# rec_seeed.net
KiCad netlist of a schematic drawn in EAGLE
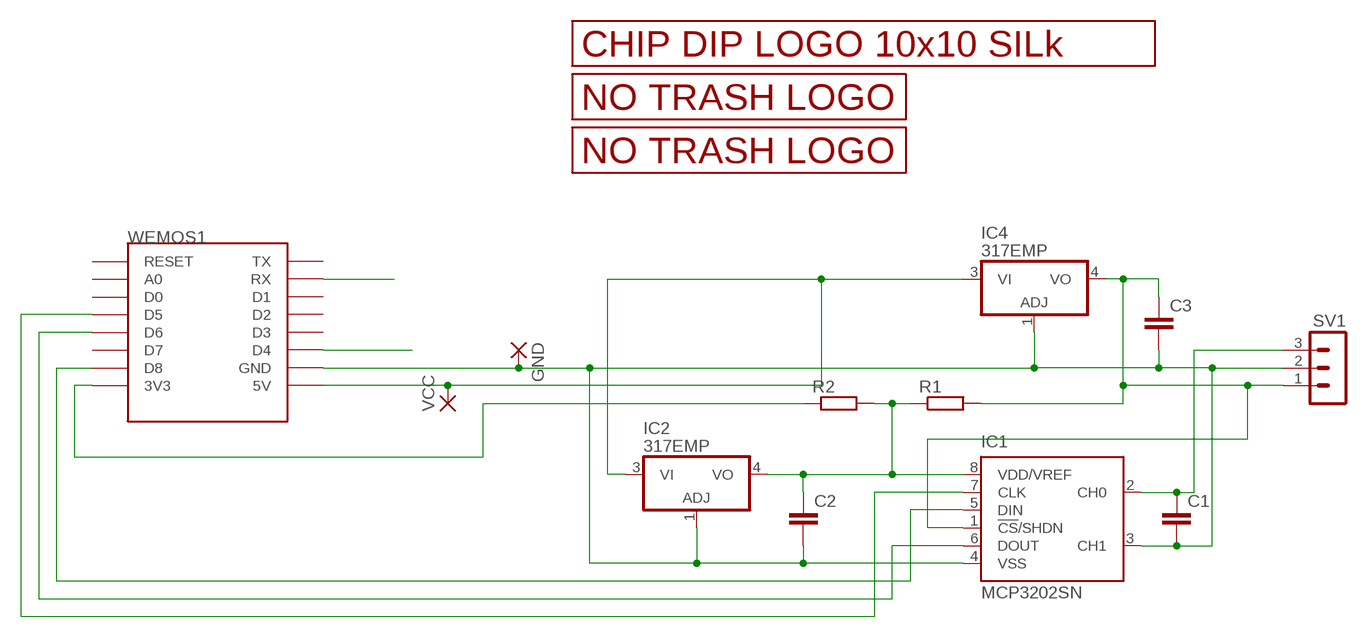
[diagram p0: schematic, sheet 1]

(export (version "E")
  (design (tool "Eeschema 10.0.6"))
  (components
    (comp (ref "C1")
      (value "C-EUC0805")
      (footprint "eagle-import:C0805")
      (libsource (lib "eagle-import") (part "C-EUC0805"))
    )
    (comp (ref "C2")
      (value "C-EUC0805")
      (footprint "eagle-import:C0805")
      (libsource (lib "eagle-import") (part "C-EUC0805"))
    )
    (comp (ref "C3")
      (value "C-EUC0805")
      (footprint "eagle-import:C0805")
      (libsource (lib "eagle-import") (part "C-EUC0805"))
    )
    (comp (ref "GND")
      (value "SMD1.36X3")
      (footprint "eagle-import:SMD1,36-3")
      (libsource (lib "eagle-import") (part "SMD1.36X3"))
    )
    (comp (ref "IC1")
      (value "MCP3202SN")
      (footprint "eagle-import:SO-08")
      (fields (field (name "MF") "MICROCHIP") (field (name "MPN") "MCP3202-CI/SN"))
      (libsource (lib "eagle-import") (part "MCP3202SN"))
    )
    (comp (ref "IC2")
      (value "317EMP")
      (footprint "eagle-import:SOT223")
      (libsource (lib "eagle-import") (part "317EMP"))
    )
    (comp (ref "IC4")
      (value "317EMP")
      (footprint "eagle-import:SOT223")
      (libsource (lib "eagle-import") (part "317EMP"))
    )
    (comp (ref "R1")
      (value "R-EU_M0805")
      (footprint "eagle-import:M0805")
      (libsource (lib "eagle-import") (part "R-EU_M0805"))
    )
    (comp (ref "R2")
      (value "R-EU_M0805")
      (footprint "eagle-import:M0805")
      (libsource (lib "eagle-import") (part "R-EU_M0805"))
    )
    (comp (ref "SV1")
      (value "MA03-1")
      (footprint "eagle-import:MA03-1")
      (libsource (lib "eagle-import") (part "MA03-1"))
    )
    (comp (ref "U$1")
      (value "LOGO_NO_TRASHNO_TRASH")
      (footprint "eagle-import:LOGO_ROHS_NO_TRASH")
      (libsource (lib "eagle-import") (part "LOGO_NO_TRASHNO_TRASH"))
    )
    (comp (ref "U$2")
      (value "LOGO_10X10_SILK")
      (footprint "eagle-import:LOGO2_10X10_SILK")
      (libsource (lib "eagle-import") (part "LOGO_10X10_SILK"))
    )
    (comp (ref "U$3")
      (value "LOGO_NO_TRASHROHS")
      (footprint "eagle-import:LOGO_ROHS_SYM")
      (libsource (lib "eagle-import") (part "LOGO_NO_TRASHROHS"))
    )
    (comp (ref "VCC")
      (value "SMD1.36X3")
      (footprint "eagle-import:SMD1,36-3")
      (libsource (lib "eagle-import") (part "SMD1.36X3"))
    )
    (comp (ref "WEMOS1")
      (value "WEMOS-D1-MININOTXT")
      (footprint "eagle-import:WEMOS_D1_MINI_NOTXT")
      (libsource (lib "eagle-import") (part "WEMOS-D1-MININOTXT"))
    )
  )
  (nets
    (net (code "1") (name "Net-(GND-P)") (class "Default")
      (node (ref "C1") (pin "2") (pinfunction "2_2") (pintype "passive"))
      (node (ref "C2") (pin "2") (pinfunction "2_2") (pintype "passive"))
      (node (ref "C3") (pin "2") (pinfunction "2_2") (pintype "passive"))
      (node (ref "GND") (pin "P$1") (pinfunction "P_P$1") (pintype "passive"))
      (node (ref "IC1") (pin "3") (pinfunction "CH1_3") (pintype "input"))
      (node (ref "IC1") (pin "4") (pinfunction "VSS_4") (pintype "input"))
      (node (ref "IC2") (pin "1") (pinfunction "ADJ_1") (pintype "input"))
      (node (ref "IC4") (pin "1") (pinfunction "ADJ_1") (pintype "input"))
      (node (ref "SV1") (pin "2") (pinfunction "2_2") (pintype "passive"))
      (node (ref "WEMOS1") (pin "GND") (pinfunction "GND_GND") (pintype "bidirectional"))
    )
    (net (code "2") (name "Net-(IC1-CH0)") (class "Default")
      (node (ref "C1") (pin "1") (pinfunction "1_1") (pintype "passive"))
      (node (ref "IC1") (pin "2") (pinfunction "CH0_2") (pintype "input"))
      (node (ref "SV1") (pin "3") (pinfunction "3_3") (pintype "passive"))
    )
    (net (code "3") (name "Net-(IC1-CLK)") (class "Default")
      (node (ref "IC1") (pin "7") (pinfunction "CLK_7") (pintype "input"))
      (node (ref "WEMOS1") (pin "D5") (pinfunction "D5_D5") (pintype "bidirectional"))
    )
    (net (code "4") (name "Net-(IC1-DIN)") (class "Default")
      (node (ref "IC1") (pin "5") (pinfunction "DIN_5") (pintype "input"))
      (node (ref "WEMOS1") (pin "D8") (pinfunction "D8_D8") (pintype "bidirectional"))
    )
    (net (code "5") (name "Net-(IC1-DOUT)") (class "Default")
      (node (ref "IC1") (pin "6") (pinfunction "DOUT_6") (pintype "input"))
      (node (ref "WEMOS1") (pin "D6") (pinfunction "D6_D6") (pintype "bidirectional"))
    )
    (net (code "6") (name "Net-(IC1-VDD{slash}VREF)") (class "Default")
      (node (ref "C2") (pin "1") (pinfunction "1_1") (pintype "passive"))
      (node (ref "IC1") (pin "8") (pinfunction "VDD/VREF_8") (pintype "input"))
      (node (ref "IC2") (pin "4") (pinfunction "VO_4") (pintype "passive"))
      (node (ref "R1") (pin "1") (pinfunction "1_1") (pintype "passive"))
      (node (ref "R2") (pin "2") (pinfunction "2_2") (pintype "passive"))
    )
    (net (code "7") (name "Net-(IC1-~{CS}{slash}SHDN)") (class "Default")
      (node (ref "C3") (pin "1") (pinfunction "1_1") (pintype "passive"))
      (node (ref "IC1") (pin "1") (pinfunction "~{CS}/SHDN_1") (pintype "input"))
      (node (ref "IC4") (pin "4") (pinfunction "VO_4") (pintype "passive"))
      (node (ref "R1") (pin "2") (pinfunction "2_2") (pintype "passive"))
      (node (ref "SV1") (pin "1") (pinfunction "1_1") (pintype "passive"))
    )
    (net (code "8") (name "Net-(IC2-VI)") (class "Default")
      (node (ref "IC2") (pin "3") (pinfunction "VI_3") (pintype "input"))
      (node (ref "IC4") (pin "3") (pinfunction "VI_3") (pintype "input"))
      (node (ref "VCC") (pin "P$1") (pinfunction "P_P$1") (pintype "passive"))
      (node (ref "WEMOS1") (pin "5V") (pinfunction "5V_5V") (pintype "bidirectional"))
    )
    (net (code "9") (name "Net-(R2-Pad1)") (class "Default")
      (node (ref "R2") (pin "1") (pinfunction "1_1") (pintype "passive"))
      (node (ref "WEMOS1") (pin "3V3") (pinfunction "3V3_3V3") (pintype "bidirectional"))
    )
    (net (code "10") (name "unconnected-(WEMOS1-PadA0)") (class "Default")
      (node (ref "WEMOS1") (pin "A0") (pinfunction "A0_A0") (pintype "bidirectional"))
    )
    (net (code "11") (name "unconnected-(WEMOS1-PadD0)") (class "Default")
      (node (ref "WEMOS1") (pin "D0") (pinfunction "D0_D0") (pintype "bidirectional"))
    )
    (net (code "12") (name "unconnected-(WEMOS1-PadD1)") (class "Default")
      (node (ref "WEMOS1") (pin "D1") (pinfunction "D1_D1") (pintype "bidirectional"))
    )
    (net (code "13") (name "unconnected-(WEMOS1-PadD2)") (class "Default")
      (node (ref "WEMOS1") (pin "D2") (pinfunction "D2_D2") (pintype "bidirectional"))
    )
    (net (code "14") (name "unconnected-(WEMOS1-PadD3)") (class "Default")
      (node (ref "WEMOS1") (pin "D3") (pinfunction "D3_D3") (pintype "bidirectional"))
    )
    (net (code "15") (name "unconnected-(WEMOS1-PadD4)") (class "Default")
      (node (ref "WEMOS1") (pin "D4") (pinfunction "D4_D4") (pintype "bidirectional"))
    )
    (net (code "16") (name "unconnected-(WEMOS1-PadD7)") (class "Default")
      (node (ref "WEMOS1") (pin "D7") (pinfunction "D7_D7") (pintype "bidirectional"))
    )
    (net (code "17") (name "unconnected-(WEMOS1-PadRESET)") (class "Default")
      (node (ref "WEMOS1") (pin "RESET") (pinfunction "RESET_RESET") (pintype "bidirectional"))
    )
    (net (code "18") (name "unconnected-(WEMOS1-PadRX)") (class "Default")
      (node (ref "WEMOS1") (pin "RX") (pinfunction "RX_RX") (pintype "bidirectional"))
    )
    (net (code "19") (name "unconnected-(WEMOS1-PadTX)") (class "Default")
      (node (ref "WEMOS1") (pin "TX") (pinfunction "TX_TX") (pintype "bidirectional"))
    )
  )
)
